# untitled.net
KiCad netlist of a schematic drawn in EAGLE
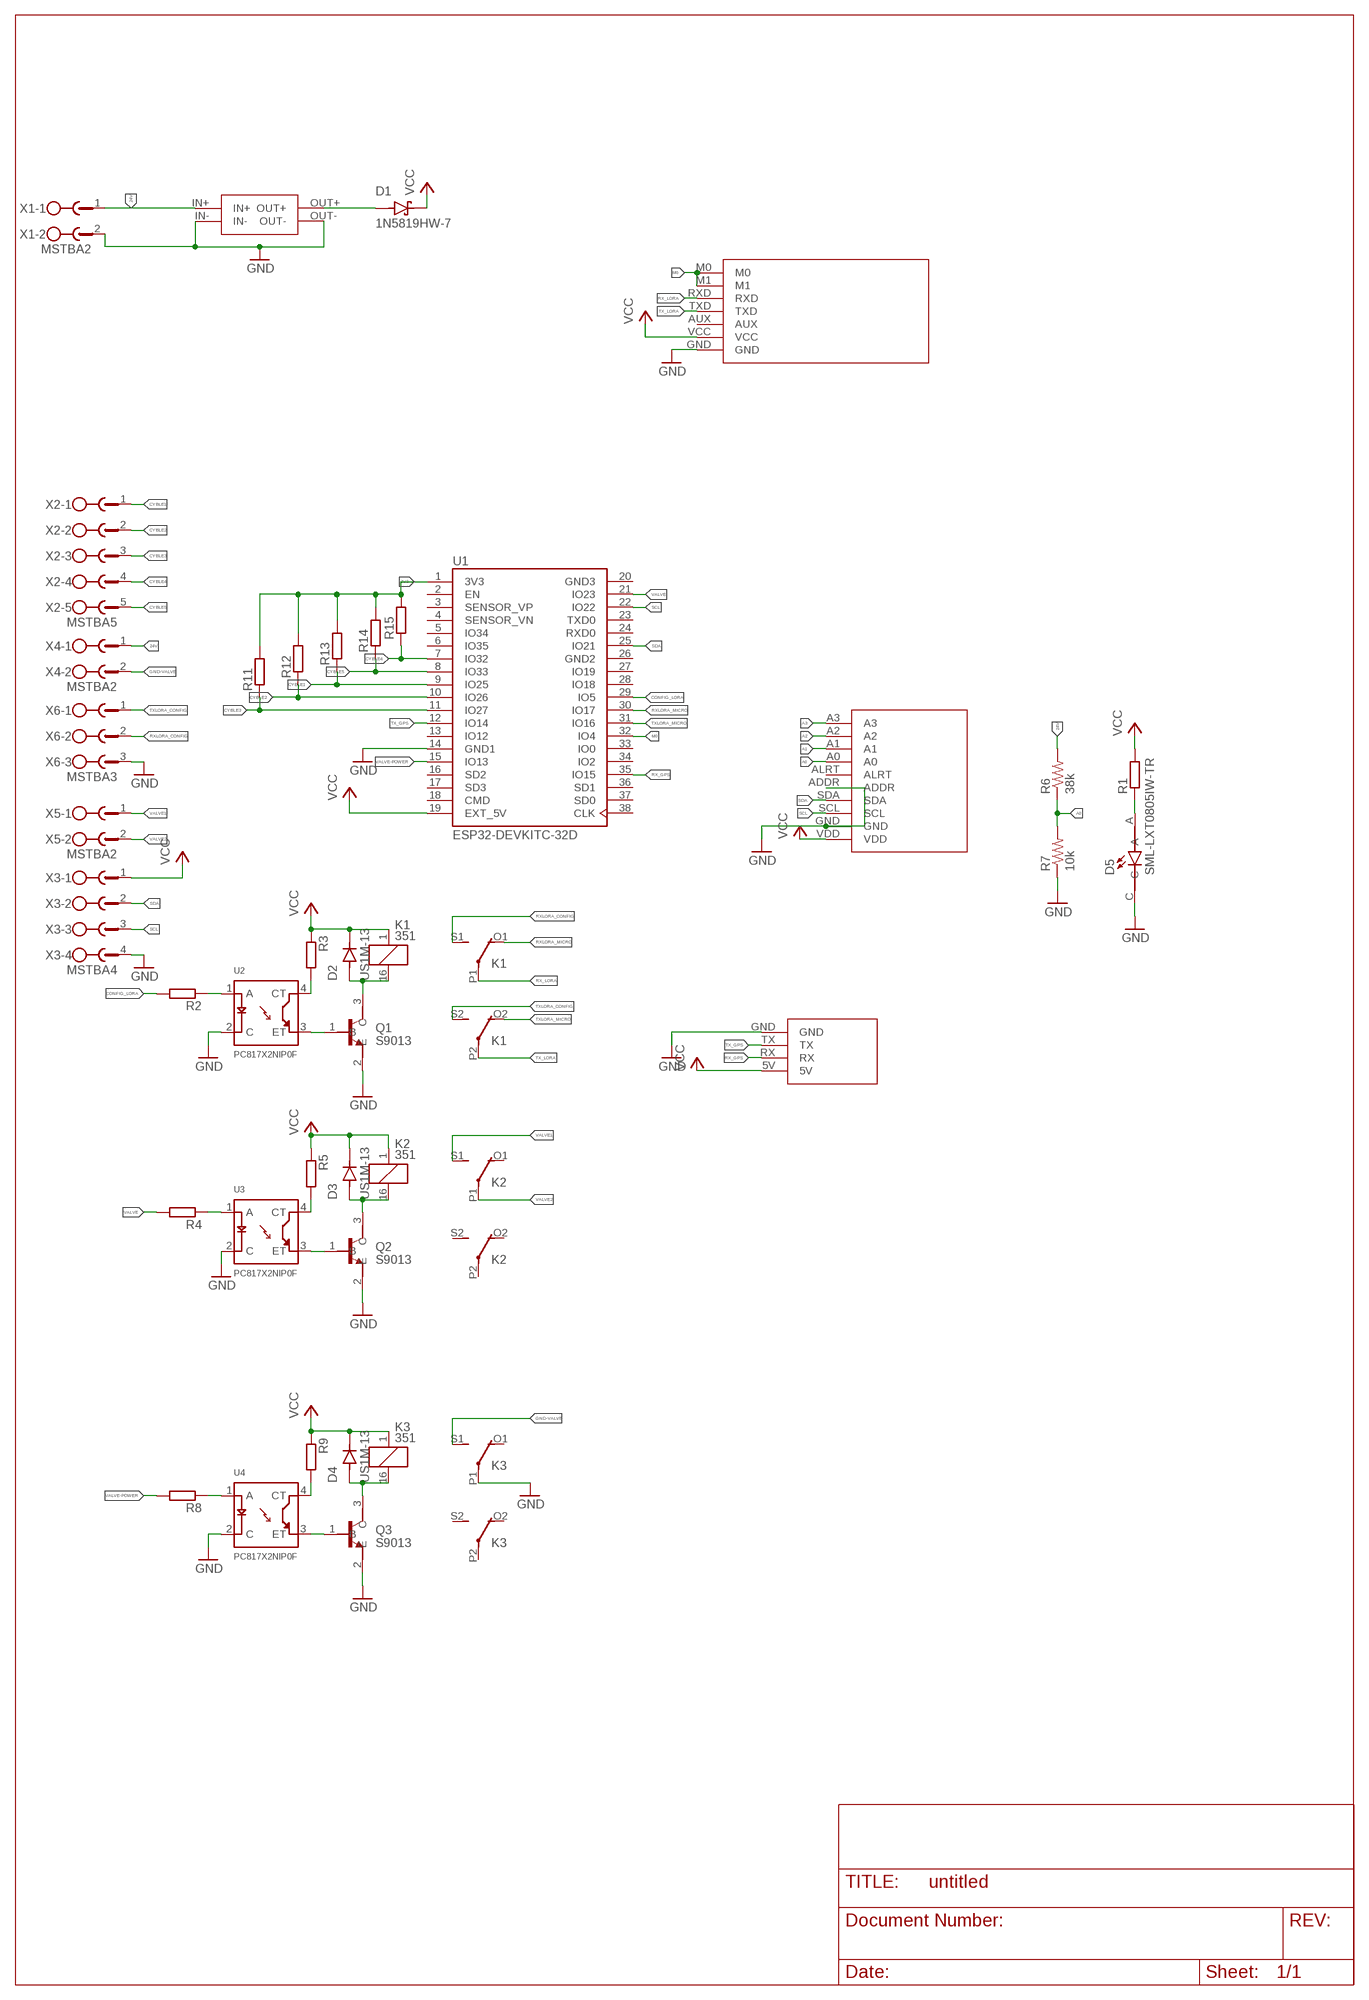
[diagram p0: schematic, sheet 1]

(export (version "E")
  (design (tool "Eeschema 10.0.6"))
  (components
    (comp (ref "ADS1")
      (value "ADS1115")
      (footprint "eagle-import:ADS1115")
      (libsource (lib "eagle-import") (part "ADS1115"))
    )
    (comp (ref "D1")
      (value "1N5819HW-7")
      (footprint "eagle-import:SOD3715X145N")
      (fields (field (name "MF") "Diodes Inc."))
      (libsource (lib "eagle-import") (part "1N5819HW-7"))
    )
    (comp (ref "D2")
      (value "US1M-13")
      (footprint "eagle-import:DIOM5226X240N")
      (fields (field (name "MF") "Diodes Incorporated"))
      (libsource (lib "eagle-import") (part "US1M-13"))
    )
    (comp (ref "D3")
      (value "US1M-13")
      (footprint "eagle-import:DIOM5226X240N")
      (fields (field (name "MF") "Diodes Incorporated"))
      (libsource (lib "eagle-import") (part "US1M-13"))
    )
    (comp (ref "D4")
      (value "US1M-13")
      (footprint "eagle-import:DIOM5226X240N")
      (fields (field (name "MF") "Diodes Incorporated"))
      (libsource (lib "eagle-import") (part "US1M-13"))
    )
    (comp (ref "D5")
      (value "SML-LXT0805IW-TR")
      (footprint "eagle-import:LEDC2012X120N")
      (fields (field (name "MF") "Lumex Opto/Components"))
      (libsource (lib "eagle-import") (part "SML-LXT0805IW-TR"))
    )
    (comp (ref "EBYTEE220-900T22D1")
      (value "EBYTEE220-900T22D")
      (footprint "eagle-import:EBYTEE220-900T22D")
      (libsource (lib "eagle-import") (part "EBYTEE220-900T22D"))
    )
    (comp (ref "K1")
      (value "351")
      (footprint "eagle-import:351")
      (libsource (lib "eagle-import") (part "351"))
    )
    (comp (ref "K2")
      (value "351")
      (footprint "eagle-import:351")
      (libsource (lib "eagle-import") (part "351"))
    )
    (comp (ref "K3")
      (value "351")
      (footprint "eagle-import:351")
      (libsource (lib "eagle-import") (part "351"))
    )
    (comp (ref "MINI1")
      (value "MINI560")
      (footprint "eagle-import:MINI560")
      (libsource (lib "eagle-import") (part "MINI560"))
    )
    (comp (ref "NEO-6MGPS1")
      (value "NEO-6MGPS")
      (footprint "eagle-import:NEO-6MGPS")
      (libsource (lib "eagle-import") (part "NEO-6MGPS"))
    )
    (comp (ref "Q1")
      (value "S9013")
      (footprint "eagle-import:SOT95P240X120-3N")
      (fields (field (name "MF") "JCET"))
      (libsource (lib "eagle-import") (part "S9013"))
    )
    (comp (ref "Q2")
      (value "S9013")
      (footprint "eagle-import:SOT95P240X120-3N")
      (fields (field (name "MF") "JCET"))
      (libsource (lib "eagle-import") (part "S9013"))
    )
    (comp (ref "Q3")
      (value "S9013")
      (footprint "eagle-import:SOT95P240X120-3N")
      (fields (field (name "MF") "JCET"))
      (libsource (lib "eagle-import") (part "S9013"))
    )
    (comp (ref "R1")
      (value "R-EU_R0805")
      (footprint "eagle-import:R0805")
      (libsource (lib "eagle-import") (part "R-EU_R0805"))
    )
    (comp (ref "R2")
      (value "R-EU_R0805")
      (footprint "eagle-import:R0805")
      (libsource (lib "eagle-import") (part "R-EU_R0805"))
    )
    (comp (ref "R3")
      (value "R-EU_R0805")
      (footprint "eagle-import:R0805")
      (libsource (lib "eagle-import") (part "R-EU_R0805"))
    )
    (comp (ref "R4")
      (value "R-EU_R0805")
      (footprint "eagle-import:R0805")
      (libsource (lib "eagle-import") (part "R-EU_R0805"))
    )
    (comp (ref "R5")
      (value "R-EU_R0805")
      (footprint "eagle-import:R0805")
      (libsource (lib "eagle-import") (part "R-EU_R0805"))
    )
    (comp (ref "R6")
      (value "38k")
      (footprint "eagle-import:0207_12")
      (libsource (lib "eagle-import") (part "R-US_0207/12"))
    )
    (comp (ref "R7")
      (value "10k")
      (footprint "eagle-import:0207_12")
      (libsource (lib "eagle-import") (part "R-US_0207/12"))
    )
    (comp (ref "R8")
      (value "R-EU_R0805")
      (footprint "eagle-import:R0805")
      (libsource (lib "eagle-import") (part "R-EU_R0805"))
    )
    (comp (ref "R9")
      (value "R-EU_R0805")
      (footprint "eagle-import:R0805")
      (libsource (lib "eagle-import") (part "R-EU_R0805"))
    )
    (comp (ref "R11")
      (value "R-EU_R0805")
      (footprint "eagle-import:R0805")
      (libsource (lib "eagle-import") (part "R-EU_R0805"))
    )
    (comp (ref "R12")
      (value "R-EU_R0805")
      (footprint "eagle-import:R0805")
      (libsource (lib "eagle-import") (part "R-EU_R0805"))
    )
    (comp (ref "R13")
      (value "R-EU_R0805")
      (footprint "eagle-import:R0805")
      (libsource (lib "eagle-import") (part "R-EU_R0805"))
    )
    (comp (ref "R14")
      (value "R-EU_R0805")
      (footprint "eagle-import:R0805")
      (libsource (lib "eagle-import") (part "R-EU_R0805"))
    )
    (comp (ref "R15")
      (value "R-EU_R0805")
      (footprint "eagle-import:R0805")
      (libsource (lib "eagle-import") (part "R-EU_R0805"))
    )
    (comp (ref "U1")
      (value "ESP32-DEVKITC-32D")
      (footprint "eagle-import:MODULE_ESP32-DEVKITC-32D")
      (fields (field (name "MF") "Espressif Systems"))
      (libsource (lib "eagle-import") (part "ESP32-DEVKITC-32D"))
    )
    (comp (ref "U2")
      (value "PC817X2NIP0F")
      (footprint "eagle-import:SOT254P975X400-4N")
      (fields (field (name "MF") "Sharp Microelectronics"))
      (libsource (lib "eagle-import") (part "PC817X2NIP0F"))
    )
    (comp (ref "U3")
      (value "PC817X2NIP0F")
      (footprint "eagle-import:SOT254P975X400-4N")
      (fields (field (name "MF") "Sharp Microelectronics"))
      (libsource (lib "eagle-import") (part "PC817X2NIP0F"))
    )
    (comp (ref "U4")
      (value "PC817X2NIP0F")
      (footprint "eagle-import:SOT254P975X400-4N")
      (fields (field (name "MF") "Sharp Microelectronics"))
      (libsource (lib "eagle-import") (part "PC817X2NIP0F"))
    )
    (comp (ref "X1")
      (value "MSTBA2")
      (footprint "eagle-import:MSTBA2")
      (fields (field (name "MF") "FARNELL") (field (name "MPN") "1757242"))
      (libsource (lib "eagle-import") (part "MSTBA2"))
    )
    (comp (ref "X2")
      (value "MSTBA5")
      (footprint "eagle-import:MSTBA5")
      (fields (field (name "MPN") "1757271"))
      (libsource (lib "eagle-import") (part "MSTBA5"))
    )
    (comp (ref "X3")
      (value "MSTBA4")
      (footprint "eagle-import:MSTBA4")
      (fields (field (name "MF") "FARNELL") (field (name "MPN") "1757268"))
      (libsource (lib "eagle-import") (part "MSTBA4"))
    )
    (comp (ref "X4")
      (value "MSTBA2")
      (footprint "eagle-import:MSTBA2")
      (fields (field (name "MF") "FARNELL") (field (name "MPN") "1757242"))
      (libsource (lib "eagle-import") (part "MSTBA2"))
    )
    (comp (ref "X5")
      (value "MSTBA2")
      (footprint "eagle-import:MSTBA2")
      (fields (field (name "MF") "FARNELL") (field (name "MPN") "1757242"))
      (libsource (lib "eagle-import") (part "MSTBA2"))
    )
    (comp (ref "X6")
      (value "MSTBA3")
      (footprint "eagle-import:MSTBA3")
      (fields (field (name "MF") "FARNELL") (field (name "MPN") "1757255"))
      (libsource (lib "eagle-import") (part "MSTBA3"))
    )
  )
  (nets
    (net (code "1") (name "/GND2") (class "Default")
      (node (ref "U1") (pin "26") (pinfunction "GND2_26") (pintype "power_in"))
    )
    (net (code "2") (name "/GND3") (class "Default")
      (node (ref "U1") (pin "20") (pinfunction "GND3_20") (pintype "power_in"))
    )
    (net (code "3") (name "3V3") (class "Default")
      (node (ref "R11") (pin "2") (pinfunction "2_2") (pintype "passive"))
      (node (ref "R12") (pin "2") (pinfunction "2_2") (pintype "passive"))
      (node (ref "R13") (pin "2") (pinfunction "2_2") (pintype "passive"))
      (node (ref "R14") (pin "2") (pinfunction "2_2") (pintype "passive"))
      (node (ref "R15") (pin "2") (pinfunction "2_2") (pintype "passive"))
      (node (ref "U1") (pin "1") (pinfunction "3V3_1") (pintype "power_in"))
    )
    (net (code "4") (name "24V") (class "Default")
      (node (ref "MINI1") (pin "IN+") (pinfunction "IN+_IN+") (pintype "bidirectional"))
      (node (ref "R6") (pin "2") (pinfunction "2_2") (pintype "passive"))
      (node (ref "X1") (pin "1") (pinfunction "1_1") (pintype "passive"))
      (node (ref "X4") (pin "1") (pinfunction "1_1") (pintype "passive"))
    )
    (net (code "5") (name "A0") (class "Default")
      (node (ref "ADS1") (pin "A0") (pinfunction "A0_A0") (pintype "bidirectional"))
      (node (ref "R6") (pin "1") (pinfunction "1_1") (pintype "passive"))
      (node (ref "R7") (pin "2") (pinfunction "2_2") (pintype "passive"))
    )
    (net (code "6") (name "A1") (class "Default")
      (node (ref "ADS1") (pin "A1") (pinfunction "A1_A1") (pintype "bidirectional"))
    )
    (net (code "7") (name "A2") (class "Default")
      (node (ref "ADS1") (pin "A2") (pinfunction "A2_A2") (pintype "bidirectional"))
    )
    (net (code "8") (name "A3") (class "Default")
      (node (ref "ADS1") (pin "A3") (pinfunction "A3_A3") (pintype "bidirectional"))
    )
    (net (code "9") (name "CONFIG_LORA") (class "Default")
      (node (ref "R2") (pin "2") (pinfunction "2_2") (pintype "passive"))
      (node (ref "U1") (pin "29") (pinfunction "IO5_29") (pintype "bidirectional"))
    )
    (net (code "10") (name "CYBLE1") (class "Default")
      (node (ref "R13") (pin "1") (pinfunction "1_1") (pintype "passive"))
      (node (ref "U1") (pin "9") (pinfunction "IO25_9") (pintype "bidirectional"))
      (node (ref "X2") (pin "1") (pinfunction "1_1") (pintype "passive"))
    )
    (net (code "11") (name "CYBLE2") (class "Default")
      (node (ref "R12") (pin "1") (pinfunction "1_1") (pintype "passive"))
      (node (ref "U1") (pin "10") (pinfunction "IO26_10") (pintype "bidirectional"))
      (node (ref "X2") (pin "2") (pinfunction "1_2") (pintype "passive"))
    )
    (net (code "12") (name "CYBLE3") (class "Default")
      (node (ref "R11") (pin "1") (pinfunction "1_1") (pintype "passive"))
      (node (ref "U1") (pin "11") (pinfunction "IO27_11") (pintype "bidirectional"))
      (node (ref "X2") (pin "3") (pinfunction "1_3") (pintype "passive"))
    )
    (net (code "13") (name "CYBLE4") (class "Default")
      (node (ref "R15") (pin "1") (pinfunction "1_1") (pintype "passive"))
      (node (ref "U1") (pin "7") (pinfunction "IO32_7") (pintype "bidirectional"))
      (node (ref "X2") (pin "4") (pinfunction "1_4") (pintype "passive"))
    )
    (net (code "14") (name "CYBLE5") (class "Default")
      (node (ref "R14") (pin "1") (pinfunction "1_1") (pintype "passive"))
      (node (ref "U1") (pin "8") (pinfunction "IO33_8") (pintype "bidirectional"))
      (node (ref "X2") (pin "5") (pinfunction "1_5") (pintype "passive"))
    )
    (net (code "15") (name "GND") (class "Default")
      (node (ref "ADS1") (pin "ADDR") (pinfunction "ADDR_ADDR") (pintype "bidirectional"))
      (node (ref "ADS1") (pin "GND") (pinfunction "GND_GND") (pintype "bidirectional"))
      (node (ref "D5") (pin "C") (pinfunction "C_C") (pintype "passive"))
      (node (ref "EBYTEE220-900T22D1") (pin "GND") (pinfunction "GND_GND") (pintype "bidirectional"))
      (node (ref "K3") (pin "P1") (pinfunction "P_P1") (pintype "passive"))
      (node (ref "MINI1") (pin "IN-") (pinfunction "IN-_IN-") (pintype "bidirectional"))
      (node (ref "MINI1") (pin "OUT-") (pinfunction "OUT-_OUT-") (pintype "bidirectional"))
      (node (ref "NEO-6MGPS1") (pin "GND") (pinfunction "GND_GND") (pintype "bidirectional"))
      (node (ref "Q1") (pin "2") (pinfunction "E_2") (pintype "passive"))
      (node (ref "Q2") (pin "2") (pinfunction "E_2") (pintype "passive"))
      (node (ref "Q3") (pin "2") (pinfunction "E_2") (pintype "passive"))
      (node (ref "R7") (pin "1") (pinfunction "1_1") (pintype "passive"))
      (node (ref "U1") (pin "14") (pinfunction "GND1_14") (pintype "power_in"))
      (node (ref "U2") (pin "2") (pinfunction "C_2") (pintype "passive"))
      (node (ref "U3") (pin "2") (pinfunction "C_2") (pintype "passive"))
      (node (ref "U4") (pin "2") (pinfunction "C_2") (pintype "passive"))
      (node (ref "X1") (pin "2") (pinfunction "1_2") (pintype "passive"))
      (node (ref "X3") (pin "4") (pinfunction "1_4") (pintype "passive"))
      (node (ref "X6") (pin "3") (pinfunction "1_3") (pintype "passive"))
    )
    (net (code "16") (name "GND-VALVE") (class "Default")
      (node (ref "K3") (pin "S1") (pinfunction "S_S1") (pintype "passive"))
      (node (ref "X4") (pin "2") (pinfunction "1_2") (pintype "passive"))
    )
    (net (code "17") (name "M0") (class "Default")
      (node (ref "EBYTEE220-900T22D1") (pin "M0") (pinfunction "M0_M0") (pintype "bidirectional"))
      (node (ref "EBYTEE220-900T22D1") (pin "M1") (pinfunction "M1_M1") (pintype "bidirectional"))
      (node (ref "U1") (pin "32") (pinfunction "IO4_32") (pintype "bidirectional"))
    )
    (net (code "18") (name "Net-(D1-PadA)") (class "Default")
      (node (ref "D1") (pin "A") (pinfunction "A_A") (pintype "passive"))
      (node (ref "MINI1") (pin "OUT+") (pinfunction "OUT+_OUT+") (pintype "bidirectional"))
    )
    (net (code "19") (name "Net-(D5-PadA)") (class "Default")
      (node (ref "D5") (pin "A") (pinfunction "A_A") (pintype "passive"))
      (node (ref "R1") (pin "1") (pinfunction "1_1") (pintype "passive"))
    )
    (net (code "20") (name "Net-(K1A-2)") (class "Default")
      (node (ref "D2") (pin "A") (pinfunction "A_A") (pintype "passive"))
      (node (ref "K1") (pin "16") (pinfunction "2_16") (pintype "passive"))
      (node (ref "Q1") (pin "3") (pinfunction "C_3") (pintype "passive"))
    )
    (net (code "21") (name "Net-(K2A-2)") (class "Default")
      (node (ref "D3") (pin "A") (pinfunction "A_A") (pintype "passive"))
      (node (ref "K2") (pin "16") (pinfunction "2_16") (pintype "passive"))
      (node (ref "Q2") (pin "3") (pinfunction "C_3") (pintype "passive"))
    )
    (net (code "22") (name "Net-(K3A-2)") (class "Default")
      (node (ref "D4") (pin "A") (pinfunction "A_A") (pintype "passive"))
      (node (ref "K3") (pin "16") (pinfunction "2_16") (pintype "passive"))
      (node (ref "Q3") (pin "3") (pinfunction "C_3") (pintype "passive"))
    )
    (net (code "23") (name "Net-(Q1-B)") (class "Default")
      (node (ref "Q1") (pin "1") (pinfunction "B_1") (pintype "passive"))
      (node (ref "U2") (pin "3") (pinfunction "ET_3") (pintype "passive"))
    )
    (net (code "24") (name "Net-(Q2-B)") (class "Default")
      (node (ref "Q2") (pin "1") (pinfunction "B_1") (pintype "passive"))
      (node (ref "U3") (pin "3") (pinfunction "ET_3") (pintype "passive"))
    )
    (net (code "25") (name "Net-(Q3-B)") (class "Default")
      (node (ref "Q3") (pin "1") (pinfunction "B_1") (pintype "passive"))
      (node (ref "U4") (pin "3") (pinfunction "ET_3") (pintype "passive"))
    )
    (net (code "26") (name "Net-(U2-A)") (class "Default")
      (node (ref "R2") (pin "1") (pinfunction "1_1") (pintype "passive"))
      (node (ref "U2") (pin "1") (pinfunction "A_1") (pintype "passive"))
    )
    (net (code "27") (name "Net-(U2-CT)") (class "Default")
      (node (ref "R3") (pin "2") (pinfunction "2_2") (pintype "passive"))
      (node (ref "U2") (pin "4") (pinfunction "CT_4") (pintype "passive"))
    )
    (net (code "28") (name "Net-(U3-A)") (class "Default")
      (node (ref "R4") (pin "1") (pinfunction "1_1") (pintype "passive"))
      (node (ref "U3") (pin "1") (pinfunction "A_1") (pintype "passive"))
    )
    (net (code "29") (name "Net-(U3-CT)") (class "Default")
      (node (ref "R5") (pin "2") (pinfunction "2_2") (pintype "passive"))
      (node (ref "U3") (pin "4") (pinfunction "CT_4") (pintype "passive"))
    )
    (net (code "30") (name "Net-(U4-A)") (class "Default")
      (node (ref "R8") (pin "1") (pinfunction "1_1") (pintype "passive"))
      (node (ref "U4") (pin "1") (pinfunction "A_1") (pintype "passive"))
    )
    (net (code "31") (name "Net-(U4-CT)") (class "Default")
      (node (ref "R9") (pin "2") (pinfunction "2_2") (pintype "passive"))
      (node (ref "U4") (pin "4") (pinfunction "CT_4") (pintype "passive"))
    )
    (net (code "32") (name "RXLORA_CONFIG") (class "Default")
      (node (ref "K1") (pin "S1") (pinfunction "S_S1") (pintype "passive"))
      (node (ref "X6") (pin "2") (pinfunction "1_2") (pintype "passive"))
    )
    (net (code "33") (name "RXLORA_MICRO") (class "Default")
      (node (ref "K1") (pin "O1") (pinfunction "O_O1") (pintype "passive"))
      (node (ref "U1") (pin "30") (pinfunction "IO17_30") (pintype "bidirectional"))
    )
    (net (code "34") (name "RX_GPS") (class "Default")
      (node (ref "NEO-6MGPS1") (pin "RX") (pinfunction "RX_RX") (pintype "bidirectional"))
      (node (ref "U1") (pin "35") (pinfunction "IO15_35") (pintype "bidirectional"))
    )
    (net (code "35") (name "RX_LORA") (class "Default")
      (node (ref "EBYTEE220-900T22D1") (pin "RXD") (pinfunction "RXD_RXD") (pintype "bidirectional"))
      (node (ref "K1") (pin "P1") (pinfunction "P_P1") (pintype "passive"))
    )
    (net (code "36") (name "SCL") (class "Default")
      (node (ref "ADS1") (pin "SCL") (pinfunction "SCL_SCL") (pintype "bidirectional"))
      (node (ref "U1") (pin "22") (pinfunction "IO22_22") (pintype "bidirectional"))
      (node (ref "X3") (pin "3") (pinfunction "1_3") (pintype "passive"))
    )
    (net (code "37") (name "SDA") (class "Default")
      (node (ref "ADS1") (pin "SDA") (pinfunction "SDA_SDA") (pintype "bidirectional"))
      (node (ref "U1") (pin "25") (pinfunction "IO21_25") (pintype "bidirectional"))
      (node (ref "X3") (pin "2") (pinfunction "1_2") (pintype "passive"))
    )
    (net (code "38") (name "TXLORA_CONFIG") (class "Default")
      (node (ref "K1") (pin "S2") (pinfunction "S_S2") (pintype "passive"))
      (node (ref "X6") (pin "1") (pinfunction "1_1") (pintype "passive"))
    )
    (net (code "39") (name "TXLORA_MICRO") (class "Default")
      (node (ref "K1") (pin "O2") (pinfunction "O_O2") (pintype "passive"))
      (node (ref "U1") (pin "31") (pinfunction "IO16_31") (pintype "bidirectional"))
    )
    (net (code "40") (name "TX_GPS") (class "Default")
      (node (ref "NEO-6MGPS1") (pin "TX") (pinfunction "TX_TX") (pintype "bidirectional"))
      (node (ref "U1") (pin "12") (pinfunction "IO14_12") (pintype "bidirectional"))
    )
    (net (code "41") (name "TX_LORA") (class "Default")
      (node (ref "EBYTEE220-900T22D1") (pin "TXD") (pinfunction "TXD_TXD") (pintype "bidirectional"))
      (node (ref "K1") (pin "P2") (pinfunction "P_P2") (pintype "passive"))
    )
    (net (code "42") (name "VALVE") (class "Default")
      (node (ref "R4") (pin "2") (pinfunction "2_2") (pintype "passive"))
      (node (ref "U1") (pin "21") (pinfunction "IO23_21") (pintype "bidirectional"))
    )
    (net (code "43") (name "VALVE-POWER") (class "Default")
      (node (ref "R8") (pin "2") (pinfunction "2_2") (pintype "passive"))
      (node (ref "U1") (pin "15") (pinfunction "IO13_15") (pintype "bidirectional"))
    )
    (net (code "44") (name "VALVE1") (class "Default")
      (node (ref "K2") (pin "S1") (pinfunction "S_S1") (pintype "passive"))
      (node (ref "X5") (pin "1") (pinfunction "1_1") (pintype "passive"))
    )
    (net (code "45") (name "VALVE2") (class "Default")
      (node (ref "K2") (pin "P1") (pinfunction "P_P1") (pintype "passive"))
      (node (ref "X5") (pin "2") (pinfunction "1_2") (pintype "passive"))
    )
    (net (code "46") (name "VCC") (class "Default")
      (node (ref "ADS1") (pin "VDD") (pinfunction "VDD_VDD") (pintype "bidirectional"))
      (node (ref "D1") (pin "C") (pinfunction "K_C") (pintype "passive"))
      (node (ref "D2") (pin "C") (pinfunction "K_C") (pintype "passive"))
      (node (ref "D3") (pin "C") (pinfunction "K_C") (pintype "passive"))
      (node (ref "D4") (pin "C") (pinfunction "K_C") (pintype "passive"))
      (node (ref "EBYTEE220-900T22D1") (pin "VCC") (pinfunction "VCC_VCC") (pintype "bidirectional"))
      (node (ref "K1") (pin "1") (pinfunction "1_1") (pintype "passive"))
      (node (ref "K2") (pin "1") (pinfunction "1_1") (pintype "passive"))
      (node (ref "K3") (pin "1") (pinfunction "1_1") (pintype "passive"))
      (node (ref "NEO-6MGPS1") (pin "5V") (pinfunction "5V_5V") (pintype "bidirectional"))
      (node (ref "R1") (pin "2") (pinfunction "2_2") (pintype "passive"))
      (node (ref "R3") (pin "1") (pinfunction "1_1") (pintype "passive"))
      (node (ref "R5") (pin "1") (pinfunction "1_1") (pintype "passive"))
      (node (ref "R9") (pin "1") (pinfunction "1_1") (pintype "passive"))
      (node (ref "U1") (pin "19") (pinfunction "EXT_5V_19") (pintype "power_in"))
      (node (ref "X3") (pin "1") (pinfunction "1_1") (pintype "passive"))
    )
    (net (code "47") (name "unconnected-(ADS1-PadALRT)") (class "Default")
      (node (ref "ADS1") (pin "ALRT") (pinfunction "ALRT_ALRT") (pintype "bidirectional"))
    )
    (net (code "48") (name "unconnected-(EBYTEE220-900T22D1-PadAUX)") (class "Default")
      (node (ref "EBYTEE220-900T22D1") (pin "AUX") (pinfunction "AUX_AUX") (pintype "bidirectional"))
    )
    (net (code "49") (name "unconnected-(K2B-O-PadO1)") (class "Default")
      (node (ref "K2") (pin "O1") (pinfunction "O_O1") (pintype "passive"))
    )
    (net (code "50") (name "unconnected-(K2C-O-PadO2)") (class "Default")
      (node (ref "K2") (pin "O2") (pinfunction "O_O2") (pintype "passive"))
    )
    (net (code "51") (name "unconnected-(K2C-P-PadP2)") (class "Default")
      (node (ref "K2") (pin "P2") (pinfunction "P_P2") (pintype "passive"))
    )
    (net (code "52") (name "unconnected-(K2C-S-PadS2)") (class "Default")
      (node (ref "K2") (pin "S2") (pinfunction "S_S2") (pintype "passive"))
    )
    (net (code "53") (name "unconnected-(K3B-O-PadO1)") (class "Default")
      (node (ref "K3") (pin "O1") (pinfunction "O_O1") (pintype "passive"))
    )
    (net (code "54") (name "unconnected-(K3C-O-PadO2)") (class "Default")
      (node (ref "K3") (pin "O2") (pinfunction "O_O2") (pintype "passive"))
    )
    (net (code "55") (name "unconnected-(K3C-P-PadP2)") (class "Default")
      (node (ref "K3") (pin "P2") (pinfunction "P_P2") (pintype "passive"))
    )
    (net (code "56") (name "unconnected-(K3C-S-PadS2)") (class "Default")
      (node (ref "K3") (pin "S2") (pinfunction "S_S2") (pintype "passive"))
    )
    (net (code "57") (name "unconnected-(U1-CLK-Pad38)") (class "Default")
      (node (ref "U1") (pin "38") (pinfunction "CLK_38") (pintype "input"))
    )
    (net (code "58") (name "unconnected-(U1-CMD-Pad18)") (class "Default")
      (node (ref "U1") (pin "18") (pinfunction "CMD_18") (pintype "bidirectional"))
    )
    (net (code "59") (name "unconnected-(U1-EN-Pad2)") (class "Default")
      (node (ref "U1") (pin "2") (pinfunction "EN_2") (pintype "input"))
    )
    (net (code "60") (name "unconnected-(U1-IO0-Pad33)") (class "Default")
      (node (ref "U1") (pin "33") (pinfunction "IO0_33") (pintype "bidirectional"))
    )
    (net (code "61") (name "unconnected-(U1-IO2-Pad34)") (class "Default")
      (node (ref "U1") (pin "34") (pinfunction "IO2_34") (pintype "bidirectional"))
    )
    (net (code "62") (name "unconnected-(U1-IO12-Pad13)") (class "Default")
      (node (ref "U1") (pin "13") (pinfunction "IO12_13") (pintype "bidirectional"))
    )
    (net (code "63") (name "unconnected-(U1-IO18-Pad28)") (class "Default")
      (node (ref "U1") (pin "28") (pinfunction "IO18_28") (pintype "bidirectional"))
    )
    (net (code "64") (name "unconnected-(U1-IO19-Pad27)") (class "Default")
      (node (ref "U1") (pin "27") (pinfunction "IO19_27") (pintype "bidirectional"))
    )
    (net (code "65") (name "unconnected-(U1-IO34-Pad5)") (class "Default")
      (node (ref "U1") (pin "5") (pinfunction "IO34_5") (pintype "bidirectional"))
    )
    (net (code "66") (name "unconnected-(U1-IO35-Pad6)") (class "Default")
      (node (ref "U1") (pin "6") (pinfunction "IO35_6") (pintype "bidirectional"))
    )
    (net (code "67") (name "unconnected-(U1-RXD0-Pad24)") (class "Default")
      (node (ref "U1") (pin "24") (pinfunction "RXD0_24") (pintype "input"))
    )
    (net (code "68") (name "unconnected-(U1-SD0-Pad37)") (class "Default")
      (node (ref "U1") (pin "37") (pinfunction "SD0_37") (pintype "bidirectional"))
    )
    (net (code "69") (name "unconnected-(U1-SD1-Pad36)") (class "Default")
      (node (ref "U1") (pin "36") (pinfunction "SD1_36") (pintype "bidirectional"))
    )
    (net (code "70") (name "unconnected-(U1-SD2-Pad16)") (class "Default")
      (node (ref "U1") (pin "16") (pinfunction "SD2_16") (pintype "bidirectional"))
    )
    (net (code "71") (name "unconnected-(U1-SD3-Pad17)") (class "Default")
      (node (ref "U1") (pin "17") (pinfunction "SD3_17") (pintype "bidirectional"))
    )
    (net (code "72") (name "unconnected-(U1-SENSOR_VN-Pad4)") (class "Default")
      (node (ref "U1") (pin "4") (pinfunction "SENSOR_VN_4") (pintype "input"))
    )
    (net (code "73") (name "unconnected-(U1-SENSOR_VP-Pad3)") (class "Default")
      (node (ref "U1") (pin "3") (pinfunction "SENSOR_VP_3") (pintype "input"))
    )
    (net (code "74") (name "unconnected-(U1-TXD0-Pad23)") (class "Default")
      (node (ref "U1") (pin "23") (pinfunction "TXD0_23") (pintype "output"))
    )
  )
)
